# Mach_trai_tim_-_Hieu.net
KiCad netlist of a schematic drawn in Altium Designer
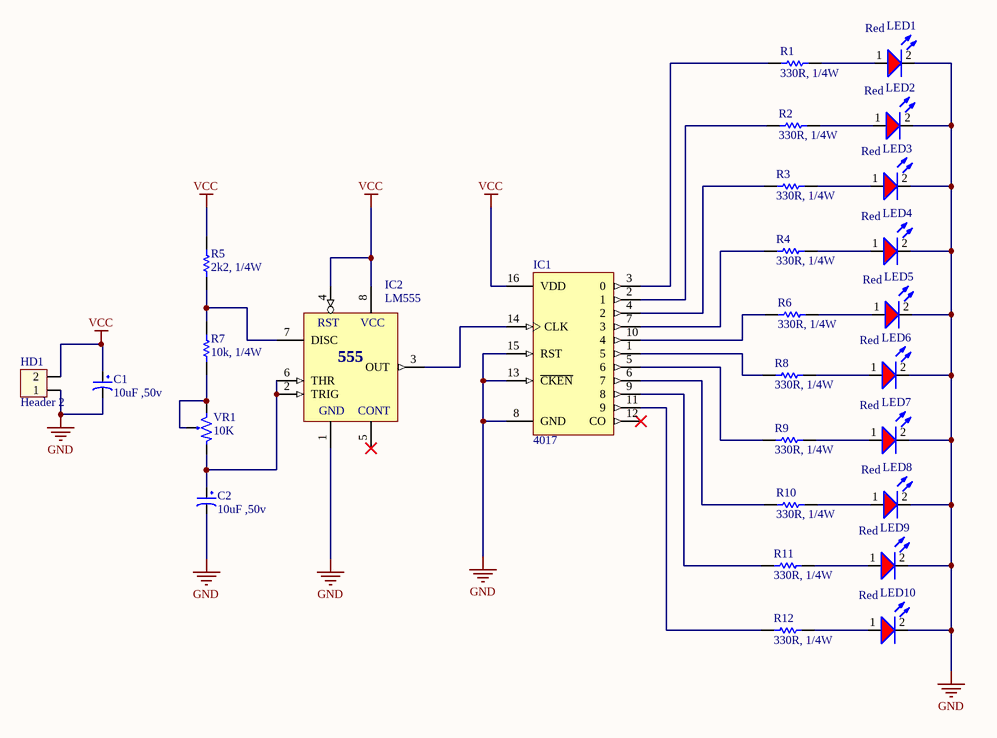
[diagram p0: Mach trai tim - Hieu.SchDoc]

(export (version "E")
  (design (tool "Eeschema 10.0.6"))
  (components
    (comp (ref "C1")
      (value "10uF ,50v")
      (footprint "CAP_1UF_50V")
      (description "Cap P  0,1uF < 22uF , 16 - 50V")
      (libsource (lib "lpson") (part "CP1"))
    )
    (comp (ref "C2")
      (value "10uF ,50v")
      (footprint "CAP_1UF_50V")
      (description "Cap P  0,1uF < 22uF , 16 - 50V")
      (libsource (lib "lpson") (part "CP1"))
    )
    (comp (ref "HD1")
      (value "Header 2")
      (footprint "CON2")
      (description "Header 2 (Green)")
      (libsource (lib "lpson") (part "Hed2"))
    )
    (comp (ref "IC1")
      (value "4017")
      (footprint "74HC4017")
      (description "Decade Counter/Divider with 10 Decoded Outputs")
      (fields (field (name "DESIGNED BY") "VanDungEvn"))
      (libsource (lib "lpson") (part "4017"))
    )
    (comp (ref "IC2")
      (value "LM555")
      (footprint "LM555")
      (description "Timer")
      (libsource (lib "lpson") (part "LM555"))
    )
    (comp (ref "LED1")
      (value "Red")
      (footprint "LED5R")
      (description "LED Red 3mm")
      (fields (field (name "Comment") "LED_R_3"))
      (libsource (lib "lpson") (part "LED_RED_3MM"))
    )
    (comp (ref "LED2")
      (value "Red")
      (footprint "LED5R")
      (description "LED Red 3mm")
      (fields (field (name "Comment") "LED_R_3"))
      (libsource (lib "lpson") (part "LED_RED_3MM"))
    )
    (comp (ref "LED3")
      (value "Red")
      (footprint "LED5R")
      (description "LED Red 3mm")
      (fields (field (name "Comment") "LED_R_3"))
      (libsource (lib "lpson") (part "LED_RED_3MM"))
    )
    (comp (ref "LED4")
      (value "Red")
      (footprint "LED5R")
      (description "LED Red 3mm")
      (fields (field (name "Comment") "LED_R_3"))
      (libsource (lib "lpson") (part "LED_RED_3MM"))
    )
    (comp (ref "LED5")
      (value "Red")
      (footprint "LED5R")
      (description "LED Red 3mm")
      (fields (field (name "Comment") "LED_R_3"))
      (libsource (lib "lpson") (part "LED_RED_3MM"))
    )
    (comp (ref "LED6")
      (value "Red")
      (footprint "LED5R")
      (description "LED Red 3mm")
      (fields (field (name "Comment") "LED_R_3"))
      (libsource (lib "lpson") (part "LED_RED_3MM"))
    )
    (comp (ref "LED7")
      (value "Red")
      (footprint "LED5R")
      (description "LED Red 3mm")
      (fields (field (name "Comment") "LED_R_3"))
      (libsource (lib "lpson") (part "LED_RED_3MM"))
    )
    (comp (ref "LED8")
      (value "Red")
      (footprint "LED5R")
      (description "LED Red 3mm")
      (fields (field (name "Comment") "LED_R_3"))
      (libsource (lib "lpson") (part "LED_RED_3MM"))
    )
    (comp (ref "LED9")
      (value "Red")
      (footprint "LED5R")
      (description "LED Red 3mm")
      (fields (field (name "Comment") "LED_R_3"))
      (libsource (lib "lpson") (part "LED_RED_3MM"))
    )
    (comp (ref "LED10")
      (value "Red")
      (footprint "LED5R")
      (description "LED Red 3mm")
      (fields (field (name "Comment") "LED_R_3"))
      (libsource (lib "lpson") (part "LED_RED_3MM"))
    )
    (comp (ref "R1")
      (value "330R, 1/4W")
      (footprint "RES 1/4W CFR25")
      (description "RES CF AXIAL-0.3 5% 1/4W 1K")
      (fields (field (name "Comment") "CF1/4W1KJ25"))
      (libsource (lib "lpson") (part "CF1/4W1KJ25"))
    )
    (comp (ref "R2")
      (value "330R, 1/4W")
      (footprint "RES 1/4W CFR25")
      (description "RES CF AXIAL-0.3 5% 1/4W 1K")
      (fields (field (name "Comment") "CF1/4W1KJ25"))
      (libsource (lib "lpson") (part "CF1/4W1KJ25"))
    )
    (comp (ref "R3")
      (value "330R, 1/4W")
      (footprint "RES 1/4W CFR25")
      (description "RES CF AXIAL-0.3 5% 1/4W 1K")
      (fields (field (name "Comment") "CF1/4W1KJ25"))
      (libsource (lib "lpson") (part "CF1/4W1KJ25"))
    )
    (comp (ref "R4")
      (value "330R, 1/4W")
      (footprint "RES 1/4W CFR25")
      (description "RES CF AXIAL-0.3 5% 1/4W 1K")
      (fields (field (name "Comment") "CF1/4W1KJ25"))
      (libsource (lib "lpson") (part "CF1/4W1KJ25"))
    )
    (comp (ref "R5")
      (value "2k2, 1/4W")
      (footprint "RES 1/4W CFR25")
      (description "RES CF AXIAL-0.3 5% 1/4W 1K")
      (fields (field (name "Comment") "CF1/4W1KJ25"))
      (libsource (lib "lpson") (part "CF1/4W1KJ25"))
    )
    (comp (ref "R6")
      (value "330R, 1/4W")
      (footprint "RES 1/4W CFR25")
      (description "RES CF AXIAL-0.3 5% 1/4W 1K")
      (fields (field (name "Comment") "CF1/4W1KJ25"))
      (libsource (lib "lpson") (part "CF1/4W1KJ25"))
    )
    (comp (ref "R7")
      (value "10k, 1/4W")
      (footprint "RES 1/4W CFR25")
      (description "RES CF AXIAL-0.3 5% 1/4W 1K")
      (fields (field (name "Comment") "CF1/4W1KJ25"))
      (libsource (lib "lpson") (part "CF1/4W1KJ25"))
    )
    (comp (ref "R8")
      (value "330R, 1/4W")
      (footprint "RES 1/4W CFR25")
      (description "RES CF AXIAL-0.3 5% 1/4W 1K")
      (fields (field (name "Comment") "CF1/4W1KJ25"))
      (libsource (lib "lpson") (part "CF1/4W1KJ25"))
    )
    (comp (ref "R9")
      (value "330R, 1/4W")
      (footprint "RES 1/4W CFR25")
      (description "RES CF AXIAL-0.3 5% 1/4W 1K")
      (fields (field (name "Comment") "CF1/4W1KJ25"))
      (libsource (lib "lpson") (part "CF1/4W1KJ25"))
    )
    (comp (ref "R10")
      (value "330R, 1/4W")
      (footprint "RES 1/4W CFR25")
      (description "RES CF AXIAL-0.3 5% 1/4W 1K")
      (fields (field (name "Comment") "CF1/4W1KJ25"))
      (libsource (lib "lpson") (part "CF1/4W1KJ25"))
    )
    (comp (ref "R11")
      (value "330R, 1/4W")
      (footprint "RES 1/4W CFR25")
      (description "RES CF AXIAL-0.3 5% 1/4W 1K")
      (fields (field (name "Comment") "CF1/4W1KJ25"))
      (libsource (lib "lpson") (part "CF1/4W1KJ25"))
    )
    (comp (ref "R12")
      (value "330R, 1/4W")
      (footprint "RES 1/4W CFR25")
      (description "RES CF AXIAL-0.3 5% 1/4W 1K")
      (fields (field (name "Comment") "CF1/4W1KJ25"))
      (libsource (lib "lpson") (part "CF1/4W1KJ25"))
    )
    (comp (ref "VR1")
      (value "10K")
      (footprint "VR1")
      (description "Var Resistor")
      (libsource (lib "lpson") (part "VR1"))
    )
  )
  (nets
    (net (code "1") (name "GND") (class "Default")
      (node (ref "C1") (pin "2") (pinfunction "2_2") (pintype "passive"))
      (node (ref "C2") (pin "2") (pinfunction "2_2") (pintype "passive"))
      (node (ref "HD1") (pin "1") (pinfunction "1_1") (pintype "passive"))
      (node (ref "IC1") (pin "13") (pinfunction "~{CKEN}_13") (pintype "input"))
      (node (ref "IC1") (pin "15") (pinfunction "RST_15") (pintype "input"))
      (node (ref "IC1") (pin "8") (pinfunction "GND_8") (pintype "power_in"))
      (node (ref "IC2") (pin "1") (pinfunction "GND_1") (pintype "power_in"))
      (node (ref "LED1") (pin "2") (pinfunction "K_2") (pintype "passive"))
      (node (ref "LED10") (pin "2") (pinfunction "K_2") (pintype "passive"))
      (node (ref "LED2") (pin "2") (pinfunction "K_2") (pintype "passive"))
      (node (ref "LED3") (pin "2") (pinfunction "K_2") (pintype "passive"))
      (node (ref "LED4") (pin "2") (pinfunction "K_2") (pintype "passive"))
      (node (ref "LED5") (pin "2") (pinfunction "K_2") (pintype "passive"))
      (node (ref "LED6") (pin "2") (pinfunction "K_2") (pintype "passive"))
      (node (ref "LED7") (pin "2") (pinfunction "K_2") (pintype "passive"))
      (node (ref "LED8") (pin "2") (pinfunction "K_2") (pintype "passive"))
      (node (ref "LED9") (pin "2") (pinfunction "K_2") (pintype "passive"))
    )
    (net (code "2") (name "Net-(IC1-0)") (class "Default")
      (node (ref "IC1") (pin "3") (pinfunction "0_3") (pintype "output"))
      (node (ref "R1") (pin "2") (pinfunction "2_2") (pintype "passive"))
    )
    (net (code "3") (name "Net-(IC1-1)") (class "Default")
      (node (ref "IC1") (pin "2") (pinfunction "1_2") (pintype "output"))
      (node (ref "R2") (pin "2") (pinfunction "2_2") (pintype "passive"))
    )
    (net (code "4") (name "Net-(IC1-2)") (class "Default")
      (node (ref "IC1") (pin "4") (pinfunction "2_4") (pintype "output"))
      (node (ref "R3") (pin "2") (pinfunction "2_2") (pintype "passive"))
    )
    (net (code "5") (name "Net-(IC1-3)") (class "Default")
      (node (ref "IC1") (pin "7") (pinfunction "3_7") (pintype "output"))
      (node (ref "R4") (pin "2") (pinfunction "2_2") (pintype "passive"))
    )
    (net (code "6") (name "Net-(IC1-4)") (class "Default")
      (node (ref "IC1") (pin "10") (pinfunction "4_10") (pintype "output"))
      (node (ref "R6") (pin "2") (pinfunction "2_2") (pintype "passive"))
    )
    (net (code "7") (name "Net-(IC1-5)") (class "Default")
      (node (ref "IC1") (pin "1") (pinfunction "5_1") (pintype "output"))
      (node (ref "R8") (pin "2") (pinfunction "2_2") (pintype "passive"))
    )
    (net (code "8") (name "Net-(IC1-6)") (class "Default")
      (node (ref "IC1") (pin "5") (pinfunction "6_5") (pintype "output"))
      (node (ref "R9") (pin "2") (pinfunction "2_2") (pintype "passive"))
    )
    (net (code "9") (name "Net-(IC1-7)") (class "Default")
      (node (ref "IC1") (pin "6") (pinfunction "7_6") (pintype "output"))
      (node (ref "R10") (pin "2") (pinfunction "2_2") (pintype "passive"))
    )
    (net (code "10") (name "Net-(IC1-8)") (class "Default")
      (node (ref "IC1") (pin "9") (pinfunction "8_9") (pintype "output"))
      (node (ref "R11") (pin "2") (pinfunction "2_2") (pintype "passive"))
    )
    (net (code "11") (name "Net-(IC1-9)") (class "Default")
      (node (ref "IC1") (pin "11") (pinfunction "9_11") (pintype "output"))
      (node (ref "R12") (pin "2") (pinfunction "2_2") (pintype "passive"))
    )
    (net (code "12") (name "Net-(IC1-CLK)") (class "Default")
      (node (ref "IC1") (pin "14") (pinfunction "CLK_14") (pintype "input"))
      (node (ref "IC2") (pin "3") (pinfunction "OUT_3") (pintype "output"))
    )
    (net (code "13") (name "Net-(IC2-DISC)") (class "Default")
      (node (ref "IC2") (pin "7") (pinfunction "DISC_7") (pintype "open_collector"))
      (node (ref "R5") (pin "1") (pinfunction "1_1") (pintype "passive"))
      (node (ref "R7") (pin "2") (pinfunction "2_2") (pintype "passive"))
    )
    (net (code "14") (name "Net-(IC2-THR)") (class "Default")
      (node (ref "C2") (pin "1") (pinfunction "1_1") (pintype "passive"))
      (node (ref "IC2") (pin "2") (pinfunction "TRIG_2") (pintype "input"))
      (node (ref "IC2") (pin "6") (pinfunction "THR_6") (pintype "input"))
      (node (ref "VR1") (pin "1") (pinfunction "1_1") (pintype "passive"))
    )
    (net (code "15") (name "Net-(LED1-A)") (class "Default")
      (node (ref "LED1") (pin "1") (pinfunction "A_1") (pintype "passive"))
      (node (ref "R1") (pin "1") (pinfunction "1_1") (pintype "passive"))
    )
    (net (code "16") (name "Net-(LED2-A)") (class "Default")
      (node (ref "LED2") (pin "1") (pinfunction "A_1") (pintype "passive"))
      (node (ref "R2") (pin "1") (pinfunction "1_1") (pintype "passive"))
    )
    (net (code "17") (name "Net-(LED3-A)") (class "Default")
      (node (ref "LED3") (pin "1") (pinfunction "A_1") (pintype "passive"))
      (node (ref "R3") (pin "1") (pinfunction "1_1") (pintype "passive"))
    )
    (net (code "18") (name "Net-(LED4-A)") (class "Default")
      (node (ref "LED4") (pin "1") (pinfunction "A_1") (pintype "passive"))
      (node (ref "R4") (pin "1") (pinfunction "1_1") (pintype "passive"))
    )
    (net (code "19") (name "Net-(LED5-A)") (class "Default")
      (node (ref "LED5") (pin "1") (pinfunction "A_1") (pintype "passive"))
      (node (ref "R6") (pin "1") (pinfunction "1_1") (pintype "passive"))
    )
    (net (code "20") (name "Net-(LED6-A)") (class "Default")
      (node (ref "LED6") (pin "1") (pinfunction "A_1") (pintype "passive"))
      (node (ref "R8") (pin "1") (pinfunction "1_1") (pintype "passive"))
    )
    (net (code "21") (name "Net-(LED7-A)") (class "Default")
      (node (ref "LED7") (pin "1") (pinfunction "A_1") (pintype "passive"))
      (node (ref "R9") (pin "1") (pinfunction "1_1") (pintype "passive"))
    )
    (net (code "22") (name "Net-(LED8-A)") (class "Default")
      (node (ref "LED8") (pin "1") (pinfunction "A_1") (pintype "passive"))
      (node (ref "R10") (pin "1") (pinfunction "1_1") (pintype "passive"))
    )
    (net (code "23") (name "Net-(LED9-A)") (class "Default")
      (node (ref "LED9") (pin "1") (pinfunction "A_1") (pintype "passive"))
      (node (ref "R11") (pin "1") (pinfunction "1_1") (pintype "passive"))
    )
    (net (code "24") (name "Net-(LED10-A)") (class "Default")
      (node (ref "LED10") (pin "1") (pinfunction "A_1") (pintype "passive"))
      (node (ref "R12") (pin "1") (pinfunction "1_1") (pintype "passive"))
    )
    (net (code "25") (name "Net-(R7-Pad1)") (class "Default")
      (node (ref "R7") (pin "1") (pinfunction "1_1") (pintype "passive"))
      (node (ref "VR1") (pin "2") (pinfunction "2_2") (pintype "passive"))
      (node (ref "VR1") (pin "3") (pinfunction "3_3") (pintype "passive"))
    )
    (net (code "26") (name "VCC") (class "Default")
      (node (ref "C1") (pin "1") (pinfunction "1_1") (pintype "passive"))
      (node (ref "HD1") (pin "2") (pinfunction "2_2") (pintype "passive"))
      (node (ref "IC1") (pin "16") (pinfunction "VDD_16") (pintype "power_in"))
      (node (ref "IC2") (pin "4") (pinfunction "RST_4") (pintype "input"))
      (node (ref "IC2") (pin "8") (pinfunction "VCC_8") (pintype "power_in"))
      (node (ref "R5") (pin "2") (pinfunction "2_2") (pintype "passive"))
    )
    (net (code "27") (name "unconnected-(IC1-CO-Pad12)") (class "Default")
      (node (ref "IC1") (pin "12") (pinfunction "CO_12") (pintype "output+no_connect"))
    )
    (net (code "28") (name "unconnected-(IC2-CONT-Pad5)") (class "Default")
      (node (ref "IC2") (pin "5") (pinfunction "CONT_5") (pintype "passive+no_connect"))
    )
  )
)
